# power-v0v675.net
KiCad netlist of a schematic drawn in Altium Designer
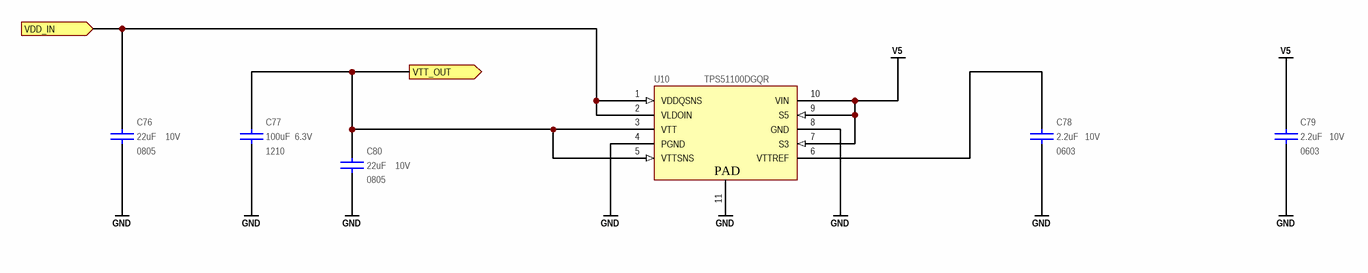
[diagram p0: power-v0v675.SchDoc]

(export (version "E")
  (design (tool "Eeschema 10.0.6"))
  (components
    (comp (ref "C76")
      (value "22uF")
      (footprint "CAPC200X125X145L45N")
      (description "Ceramic Capacitor 22uF ±20% 10V X7S 0805")
      (fields
        (field (name "MANUFACTURER") "TDK")
        (field (name "TOLERANCE") "±20%")
        (field (name "VOLTAGE") "10V")
        (field (name "PACKAGE") "0805")
      )
      (libsource (lib "") (part "CAP_1"))
    )
    (comp (ref "C77")
      (value "100uF")
      (footprint "CAPC320X250X280L50N")
      (description "Ceramic Capacitor 100uF ±20% 6.3V X6S 1210")
      (fields
        (field (name "MANUFACTURER") "TDK")
        (field (name "TOLERANCE") "±20%")
        (field (name "VOLTAGE") "6.3V")
        (field (name "PACKAGE") "1210")
      )
      (libsource (lib "") (part "CAP_1"))
    )
    (comp (ref "C78")
      (value "2.2uF")
      (footprint "CAPC160X80X90L20N")
      (description "Ceramic Capacitor 2.2uF ±20% 10V X7R 0603")
      (fields
        (field (name "MANUFACTURER") "TDK")
        (field (name "TOLERANCE") "±20%")
        (field (name "VOLTAGE") "10V")
        (field (name "PACKAGE") "0603")
      )
      (libsource (lib "generic") (part "CAP"))
    )
    (comp (ref "C79")
      (value "2.2uF")
      (footprint "CAPC160X80X90L20N")
      (description "Ceramic Capacitor 2.2uF ±20% 10V X7R 0603")
      (fields
        (field (name "MANUFACTURER") "TDK")
        (field (name "TOLERANCE") "±20%")
        (field (name "VOLTAGE") "10V")
        (field (name "PACKAGE") "0603")
      )
      (libsource (lib "generic") (part "CAP"))
    )
    (comp (ref "C80")
      (value "22uF")
      (footprint "CAPC200X125X145L45N")
      (description "Ceramic Capacitor 22uF ±20% 10V X7S 0805")
      (fields
        (field (name "MANUFACTURER") "TDK")
        (field (name "TOLERANCE") "±20%")
        (field (name "VOLTAGE") "10V")
        (field (name "PACKAGE") "0805")
      )
      (libsource (lib "") (part "CAP_1"))
    )
    (comp (ref "U10")
      (value "TPS51100DGQR")
      (footprint "SOP11P50_300X490X110L55X22T157X188N")
      (description "IC Voltage Reg DDR1/2/3 VTT")
      (fields (field (name "MANUFACTURER") "Texas Instruments"))
      (libsource (lib "Kron Library Rev 3") (part "TPS51100DGQR"))
    )
  )
  (nets
    (net (code "1") (name "/VDD_IN") (class "Default")
      (node (ref "C76") (pin "2") (pinfunction "2_2") (pintype "passive"))
      (node (ref "U10") (pin "1") (pinfunction "VDDQSNS_1") (pintype "input"))
      (node (ref "U10") (pin "2") (pinfunction "VLDOIN_2") (pintype "power_in"))
    )
    (net (code "2") (name "/VTT_OUT") (class "Default")
      (node (ref "C77") (pin "1") (pinfunction "1_1") (pintype "passive"))
      (node (ref "C80") (pin "2") (pinfunction "2_2") (pintype "passive"))
      (node (ref "U10") (pin "3") (pinfunction "VTT_3") (pintype "power_in"))
      (node (ref "U10") (pin "5") (pinfunction "VTTSNS_5") (pintype "input"))
    )
    (net (code "3") (name "GND") (class "Default")
      (node (ref "C76") (pin "1") (pinfunction "1_1") (pintype "passive"))
      (node (ref "C77") (pin "2") (pinfunction "2_2") (pintype "passive"))
      (node (ref "C78") (pin "1") (pinfunction "1_1") (pintype "passive"))
      (node (ref "C79") (pin "1") (pinfunction "1_1") (pintype "passive"))
      (node (ref "C80") (pin "1") (pinfunction "1_1") (pintype "passive"))
      (node (ref "U10") (pin "11") (pinfunction "PAD_11") (pintype "passive"))
      (node (ref "U10") (pin "4") (pinfunction "PGND_4") (pintype "power_in"))
      (node (ref "U10") (pin "8") (pinfunction "GND_8") (pintype "power_in"))
    )
    (net (code "4") (name "Net-(U10-VTTREF)") (class "Default")
      (node (ref "C78") (pin "2") (pinfunction "2_2") (pintype "passive"))
      (node (ref "U10") (pin "6") (pinfunction "VTTREF_6") (pintype "power_in"))
    )
    (net (code "5") (name "V5") (class "Default")
      (node (ref "C79") (pin "2") (pinfunction "2_2") (pintype "passive"))
      (node (ref "U10") (pin "10") (pinfunction "VIN_10") (pintype "power_in"))
      (node (ref "U10") (pin "7") (pinfunction "S3_7") (pintype "input"))
      (node (ref "U10") (pin "9") (pinfunction "S5_9") (pintype "input"))
    )
  )
)
